# MainBoard_new.net
KiCad netlist of a schematic drawn in EAGLE
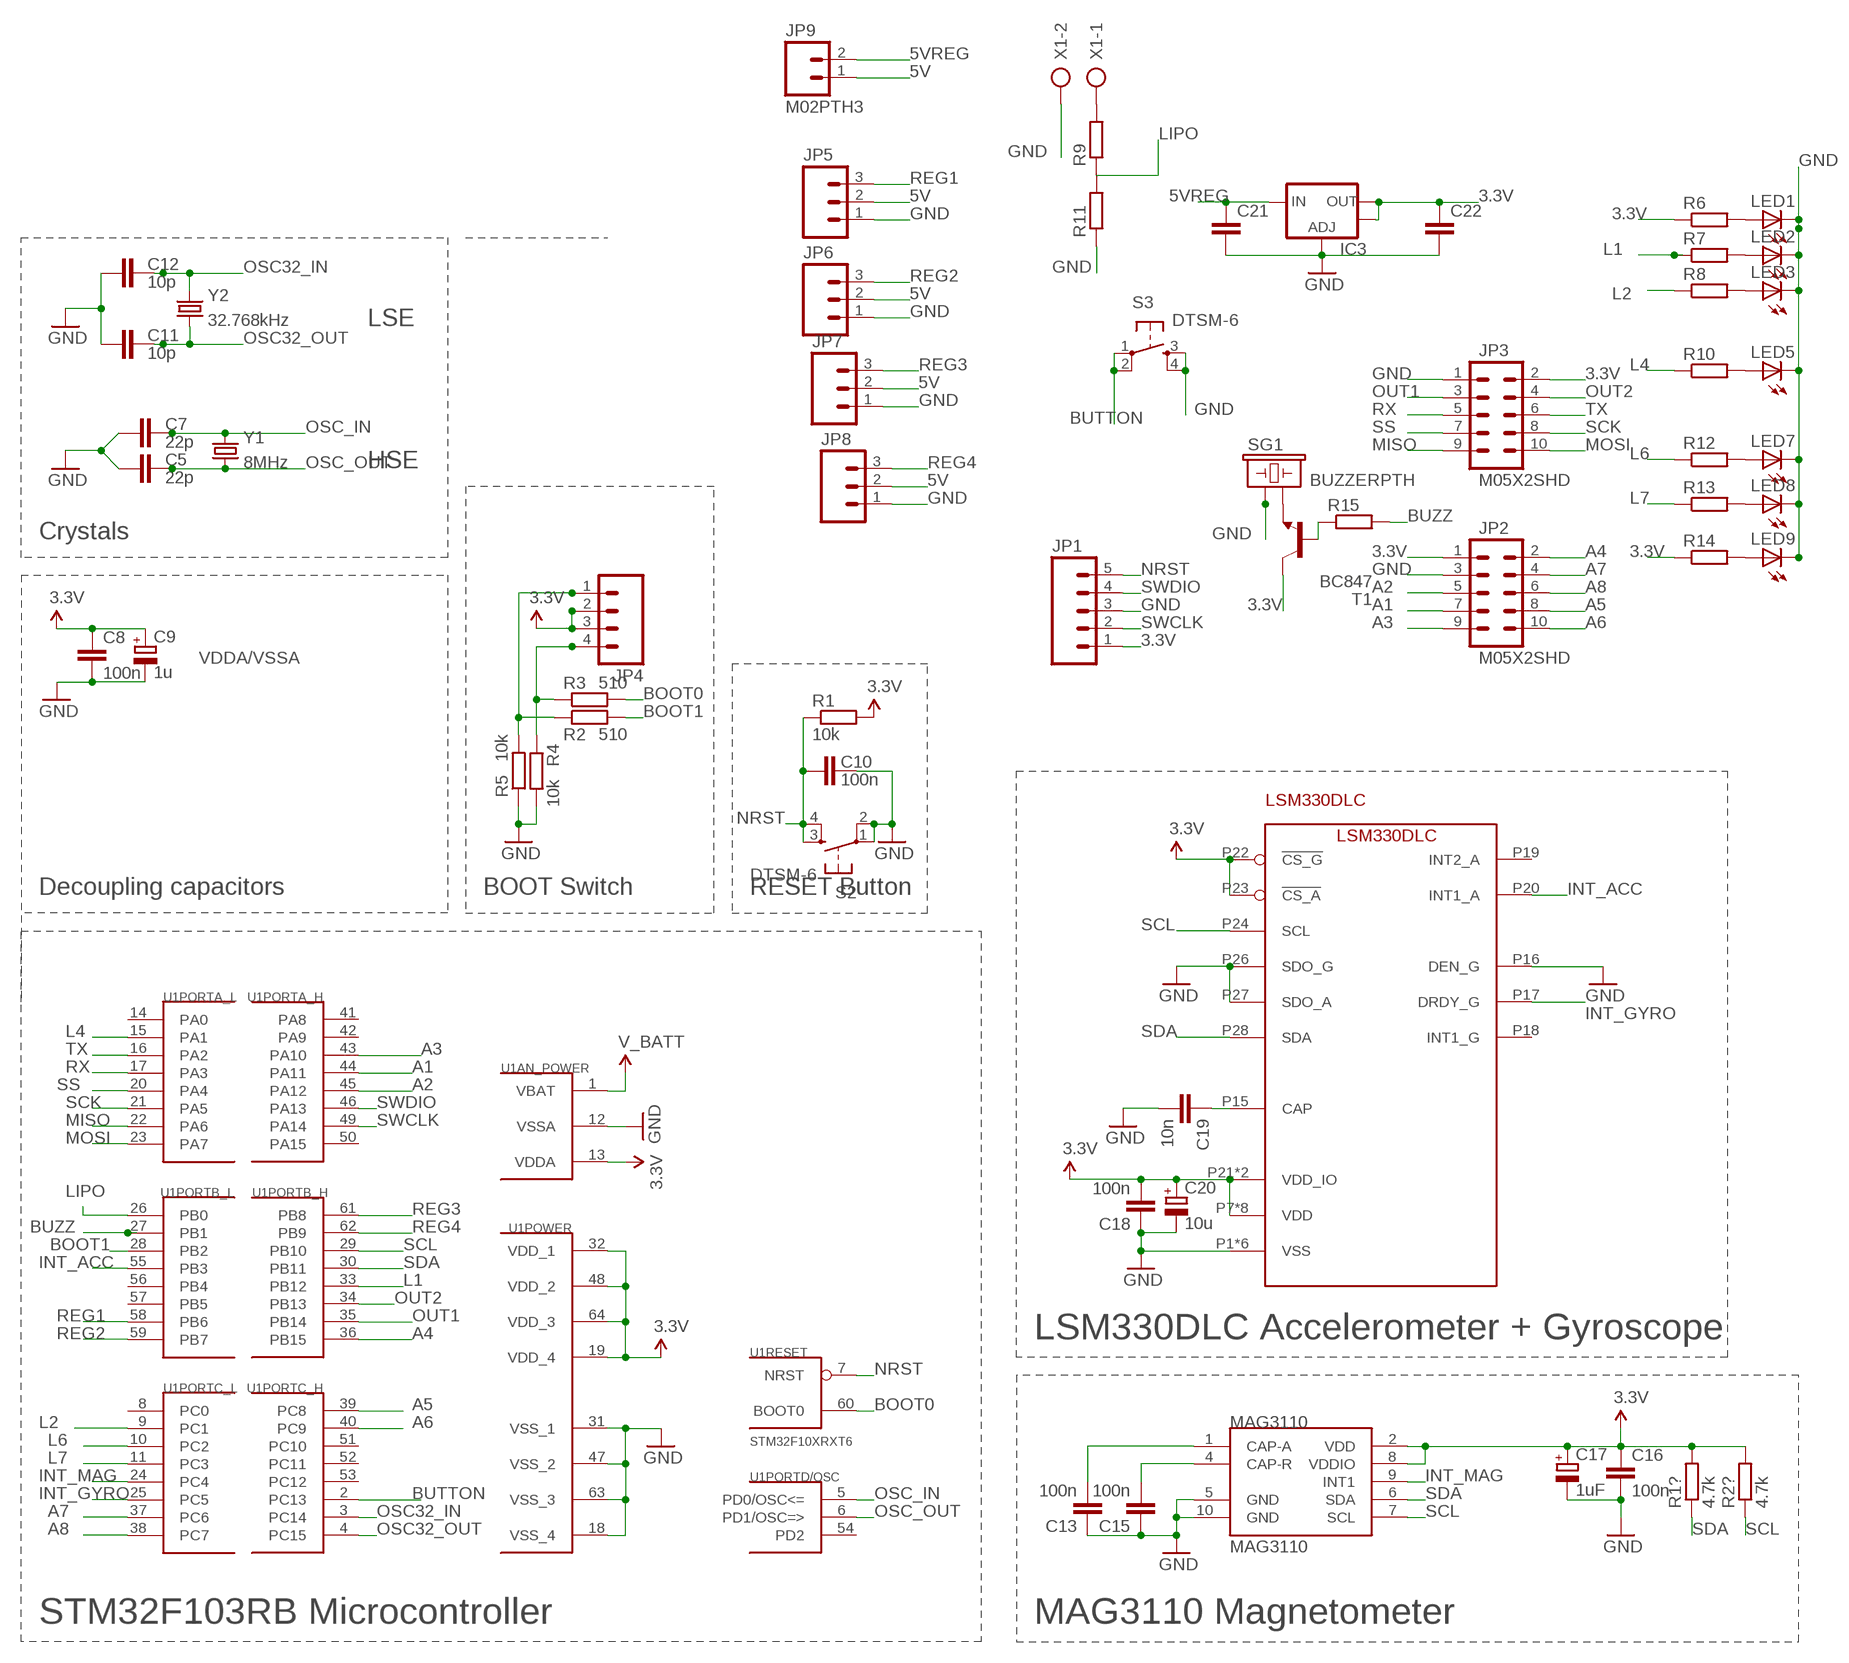
[diagram p0: schematic, sheet 1]

(export (version "E")
  (design (tool "Eeschema 10.0.6"))
  (components
    (comp (ref "C5")
      (value "22p")
      (footprint "eagle-import:C0805")
      (libsource (lib "eagle-import") (part "C-EUC0805"))
    )
    (comp (ref "C7")
      (value "22p")
      (footprint "eagle-import:C0805")
      (libsource (lib "eagle-import") (part "C-EUC0805"))
    )
    (comp (ref "C8")
      (value "100n")
      (footprint "eagle-import:C0805")
      (libsource (lib "eagle-import") (part "C-EUC0805"))
    )
    (comp (ref "C9")
      (value "1u")
      (footprint "eagle-import:SMC_A")
      (libsource (lib "eagle-import") (part "CPOL-EUSMCA"))
    )
    (comp (ref "C10")
      (value "100n")
      (footprint "eagle-import:C0805")
      (libsource (lib "eagle-import") (part "C-EUC0805"))
    )
    (comp (ref "C11")
      (value "10p")
      (footprint "eagle-import:C0805")
      (libsource (lib "eagle-import") (part "C-EUC0805"))
    )
    (comp (ref "C12")
      (value "10p")
      (footprint "eagle-import:C0805")
      (libsource (lib "eagle-import") (part "C-EUC0805"))
    )
    (comp (ref "C13")
      (value "100n")
      (footprint "eagle-import:C0805")
      (libsource (lib "eagle-import") (part "C-EUC0805"))
    )
    (comp (ref "C15")
      (value "100n")
      (footprint "eagle-import:C0805")
      (libsource (lib "eagle-import") (part "C-EUC0805"))
    )
    (comp (ref "C16")
      (value "100n")
      (footprint "eagle-import:C0805")
      (libsource (lib "eagle-import") (part "C-EUC0805"))
    )
    (comp (ref "C17")
      (value "1uF")
      (footprint "eagle-import:SMC_A")
      (libsource (lib "eagle-import") (part "CPOL-EUSMCA"))
    )
    (comp (ref "C18")
      (value "100n")
      (footprint "eagle-import:C0805")
      (libsource (lib "eagle-import") (part "resistor_C-EUC0805"))
    )
    (comp (ref "C19")
      (value "10n")
      (footprint "eagle-import:C0805")
      (libsource (lib "eagle-import") (part "resistor_C-EUC0805"))
    )
    (comp (ref "C20")
      (value "10u")
      (footprint "eagle-import:SMC_A")
      (libsource (lib "eagle-import") (part "CPOL-EUSMCA"))
    )
    (comp (ref "C21")
      (value "C-EUC0805")
      (footprint "eagle-import:C0805")
      (libsource (lib "eagle-import") (part "C-EUC0805"))
    )
    (comp (ref "C22")
      (value "C-EUC0805")
      (footprint "eagle-import:C0805")
      (libsource (lib "eagle-import") (part "C-EUC0805"))
    )
    (comp (ref "IC3")
      (value "V_REG_LM1117SOT223")
      (footprint "eagle-import:SOT223")
      (libsource (lib "eagle-import") (part "V_REG_LM1117SOT223"))
    )
    (comp (ref "JP1")
      (value "M05PTH_LONGPADS")
      (footprint "eagle-import:1X05_LONGPADS")
      (libsource (lib "eagle-import") (part "M05PTH_LONGPADS"))
    )
    (comp (ref "JP2")
      (value "M05X2SHD")
      (footprint "eagle-import:2X5-SHROUDED")
      (libsource (lib "eagle-import") (part "M05X2SHD"))
    )
    (comp (ref "JP3")
      (value "M05X2SHD")
      (footprint "eagle-import:2X5-SHROUDED")
      (libsource (lib "eagle-import") (part "M05X2SHD"))
    )
    (comp (ref "JP4")
      (value "M04LONGPADS")
      (footprint "eagle-import:1X04_LONGPADS")
      (libsource (lib "eagle-import") (part "M04LONGPADS"))
    )
    (comp (ref "JP5")
      (value "M03LONGPADS")
      (footprint "eagle-import:1X03_LONGPADS")
      (libsource (lib "eagle-import") (part "M03LONGPADS"))
    )
    (comp (ref "JP6")
      (value "M03LONGPADS")
      (footprint "eagle-import:1X03_LONGPADS")
      (libsource (lib "eagle-import") (part "M03LONGPADS"))
    )
    (comp (ref "JP7")
      (value "M03LONGPADS")
      (footprint "eagle-import:1X03_LONGPADS")
      (libsource (lib "eagle-import") (part "M03LONGPADS"))
    )
    (comp (ref "JP8")
      (value "M03LONGPADS")
      (footprint "eagle-import:1X03_LONGPADS")
      (libsource (lib "eagle-import") (part "M03LONGPADS"))
    )
    (comp (ref "JP9")
      (value "M02PTH3")
      (footprint "eagle-import:1X02_LONGPADS")
      (libsource (lib "eagle-import") (part "M02PTH3"))
    )
    (comp (ref "LED1")
      (value "LEDCHIPLED_0805")
      (footprint "eagle-import:CHIPLED_0805")
      (libsource (lib "eagle-import") (part "LEDCHIPLED_0805"))
    )
    (comp (ref "LED2")
      (value "LEDCHIPLED_0805")
      (footprint "eagle-import:CHIPLED_0805")
      (libsource (lib "eagle-import") (part "LEDCHIPLED_0805"))
    )
    (comp (ref "LED3")
      (value "LEDCHIPLED_0805")
      (footprint "eagle-import:CHIPLED_0805")
      (libsource (lib "eagle-import") (part "LEDCHIPLED_0805"))
    )
    (comp (ref "LED5")
      (value "LEDCHIPLED_0805")
      (footprint "eagle-import:CHIPLED_0805")
      (libsource (lib "eagle-import") (part "LEDCHIPLED_0805"))
    )
    (comp (ref "LED7")
      (value "LEDCHIPLED_0805")
      (footprint "eagle-import:CHIPLED_0805")
      (libsource (lib "eagle-import") (part "LEDCHIPLED_0805"))
    )
    (comp (ref "LED8")
      (value "LEDCHIPLED_0805")
      (footprint "eagle-import:CHIPLED_0805")
      (libsource (lib "eagle-import") (part "LEDCHIPLED_0805"))
    )
    (comp (ref "LED9")
      (value "LEDCHIPLED_0805")
      (footprint "eagle-import:CHIPLED_0805")
      (libsource (lib "eagle-import") (part "LEDCHIPLED_0805"))
    )
    (comp (ref "LSM330DLC")
      (value "LSM330DLC")
      (footprint "eagle-import:LGA_4X5X1P1_28L")
      (libsource (lib "eagle-import") (part "LSM330DLC"))
    )
    (comp (ref "MAG3110")
      (value "MAG3110")
      (footprint "eagle-import:DFN-10")
      (libsource (lib "eagle-import") (part "MAG3110"))
    )
    (comp (ref "R1")
      (value "10k")
      (footprint "eagle-import:R0805")
      (libsource (lib "eagle-import") (part "R-EU_R0805"))
    )
    (comp (ref "R1?")
      (value "4.7k")
      (footprint "eagle-import:R0805")
      (libsource (lib "eagle-import") (part "R-EU_R0805"))
    )
    (comp (ref "R2")
      (value "510")
      (footprint "eagle-import:R0805")
      (libsource (lib "eagle-import") (part "R-EU_R0805"))
    )
    (comp (ref "R2?")
      (value "4.7k")
      (footprint "eagle-import:R0805")
      (libsource (lib "eagle-import") (part "R-EU_R0805"))
    )
    (comp (ref "R3")
      (value "510")
      (footprint "eagle-import:R0805")
      (libsource (lib "eagle-import") (part "R-EU_R0805"))
    )
    (comp (ref "R4")
      (value "10k")
      (footprint "eagle-import:R0805")
      (libsource (lib "eagle-import") (part "R-EU_R0805"))
    )
    (comp (ref "R5")
      (value "10k")
      (footprint "eagle-import:R0805")
      (libsource (lib "eagle-import") (part "R-EU_R0805"))
    )
    (comp (ref "R6")
      (value "R-EU_M0805")
      (footprint "eagle-import:M0805")
      (libsource (lib "eagle-import") (part "resistor_R-EU_M0805"))
    )
    (comp (ref "R7")
      (value "R-EU_M0805")
      (footprint "eagle-import:M0805")
      (libsource (lib "eagle-import") (part "resistor_R-EU_M0805"))
    )
    (comp (ref "R8")
      (value "R-EU_M0805")
      (footprint "eagle-import:M0805")
      (libsource (lib "eagle-import") (part "resistor_R-EU_M0805"))
    )
    (comp (ref "R9")
      (value "R-EU_M0805")
      (footprint "eagle-import:M0805")
      (libsource (lib "eagle-import") (part "resistor_R-EU_M0805"))
    )
    (comp (ref "R10")
      (value "R-EU_M0805")
      (footprint "eagle-import:M0805")
      (libsource (lib "eagle-import") (part "resistor_R-EU_M0805"))
    )
    (comp (ref "R11")
      (value "R-EU_M0805")
      (footprint "eagle-import:M0805")
      (libsource (lib "eagle-import") (part "resistor_R-EU_M0805"))
    )
    (comp (ref "R12")
      (value "R-EU_M0805")
      (footprint "eagle-import:M0805")
      (libsource (lib "eagle-import") (part "resistor_R-EU_M0805"))
    )
    (comp (ref "R13")
      (value "R-EU_M0805")
      (footprint "eagle-import:M0805")
      (libsource (lib "eagle-import") (part "resistor_R-EU_M0805"))
    )
    (comp (ref "R14")
      (value "R-EU_M0805")
      (footprint "eagle-import:M0805")
      (libsource (lib "eagle-import") (part "resistor_R-EU_M0805"))
    )
    (comp (ref "R15")
      (value "R-EU_R0805")
      (footprint "eagle-import:R0805")
      (libsource (lib "eagle-import") (part "R-EU_R0805"))
    )
    (comp (ref "S2")
      (value "DTSM-6")
      (footprint "eagle-import:DTSM-6")
      (libsource (lib "eagle-import") (part "DTSM-6"))
    )
    (comp (ref "S3")
      (value "DTSM-6")
      (footprint "eagle-import:DTSM-6")
      (libsource (lib "eagle-import") (part "DTSM-6"))
    )
    (comp (ref "SG1")
      (value "BUZZERPTH")
      (footprint "eagle-import:BUZZER-12MM")
      (libsource (lib "eagle-import") (part "BUZZERPTH"))
    )
    (comp (ref "T1")
      (value "BC847")
      (footprint "eagle-import:SOT23")
      (libsource (lib "eagle-import") (part "BC847"))
    )
    (comp (ref "U1")
      (value "STM32F10XRXT6")
      (footprint "eagle-import:TQFP64")
      (libsource (lib "eagle-import") (part "STM32F10XRXT6"))
    )
    (comp (ref "X1")
      (value "AK300/2")
      (footprint "eagle-import:AK300_2")
      (libsource (lib "eagle-import") (part "AK300/2"))
    )
    (comp (ref "Y1")
      (value "8MHz")
      (footprint "eagle-import:HC49UP")
      (libsource (lib "eagle-import") (part "CRYSTALSMD"))
    )
    (comp (ref "Y2")
      (value "32.768kHz")
      (footprint "eagle-import:CRYSTAL-32KHZ-SMD_EPSON_MC146")
      (libsource (lib "eagle-import") (part "CRYSTALEPSONMC146"))
    )
  )
  (nets
    (net (code "1") (name "/5V") (class "Default")
      (node (ref "JP5") (pin "2") (pinfunction "2_2") (pintype "passive"))
      (node (ref "JP6") (pin "2") (pinfunction "2_2") (pintype "passive"))
      (node (ref "JP7") (pin "2") (pinfunction "2_2") (pintype "passive"))
      (node (ref "JP8") (pin "2") (pinfunction "2_2") (pintype "passive"))
      (node (ref "JP9") (pin "1") (pinfunction "1_1") (pintype "passive"))
    )
    (net (code "2") (name "/5VREG") (class "Default")
      (node (ref "C21") (pin "1") (pinfunction "1_1") (pintype "passive"))
      (node (ref "IC3") (pin "3") (pinfunction "IN_3") (pintype "input"))
      (node (ref "JP9") (pin "2") (pinfunction "2_2") (pintype "passive"))
    )
    (net (code "3") (name "/A1") (class "Default")
      (node (ref "JP2") (pin "7") (pinfunction "7_7") (pintype "passive"))
      (node (ref "U1") (pin "44") (pinfunction "PA11_44") (pintype "bidirectional"))
    )
    (net (code "4") (name "/A2") (class "Default")
      (node (ref "JP2") (pin "5") (pinfunction "5_5") (pintype "passive"))
      (node (ref "U1") (pin "45") (pinfunction "PA12_45") (pintype "bidirectional"))
    )
    (net (code "5") (name "/A3") (class "Default")
      (node (ref "JP2") (pin "9") (pinfunction "9_9") (pintype "passive"))
      (node (ref "U1") (pin "43") (pinfunction "PA10_43") (pintype "bidirectional"))
    )
    (net (code "6") (name "/A4") (class "Default")
      (node (ref "JP2") (pin "2") (pinfunction "2_2") (pintype "passive"))
      (node (ref "U1") (pin "36") (pinfunction "PB15_36") (pintype "bidirectional"))
    )
    (net (code "7") (name "/A5") (class "Default")
      (node (ref "JP2") (pin "8") (pinfunction "8_8") (pintype "passive"))
      (node (ref "U1") (pin "39") (pinfunction "PC8_39") (pintype "bidirectional"))
    )
    (net (code "8") (name "/A6") (class "Default")
      (node (ref "JP2") (pin "10") (pinfunction "10_10") (pintype "passive"))
      (node (ref "U1") (pin "40") (pinfunction "PC9_40") (pintype "bidirectional"))
    )
    (net (code "9") (name "/A7") (class "Default")
      (node (ref "JP2") (pin "4") (pinfunction "4_4") (pintype "passive"))
      (node (ref "U1") (pin "37") (pinfunction "PC6_37") (pintype "bidirectional"))
    )
    (net (code "10") (name "/A8") (class "Default")
      (node (ref "JP2") (pin "6") (pinfunction "6_6") (pintype "passive"))
      (node (ref "U1") (pin "38") (pinfunction "PC7_38") (pintype "bidirectional"))
    )
    (net (code "11") (name "/BOOT0") (class "Default")
      (node (ref "R3") (pin "2") (pinfunction "2_2") (pintype "passive"))
      (node (ref "U1") (pin "60") (pinfunction "BOOT0_60") (pintype "input"))
    )
    (net (code "12") (name "/BOOT1") (class "Default")
      (node (ref "R2") (pin "2") (pinfunction "2_2") (pintype "passive"))
      (node (ref "U1") (pin "28") (pinfunction "PB2_28") (pintype "bidirectional"))
    )
    (net (code "13") (name "/BUTTON") (class "Default")
      (node (ref "S3") (pin "1") (pinfunction "1_1") (pintype "passive"))
      (node (ref "S3") (pin "2") (pinfunction "2_2") (pintype "passive"))
      (node (ref "U1") (pin "2") (pinfunction "PC13_2") (pintype "bidirectional"))
    )
    (net (code "14") (name "/BUZZ") (class "Default")
      (node (ref "R15") (pin "2") (pinfunction "2_2") (pintype "passive"))
      (node (ref "U1") (pin "27") (pinfunction "PB1_27") (pintype "bidirectional"))
    )
    (net (code "15") (name "/INT_ACC") (class "Default")
      (node (ref "LSM330DLC") (pin "P20") (pinfunction "INT1_A_P20") (pintype "output"))
      (node (ref "U1") (pin "55") (pinfunction "PB3_55") (pintype "bidirectional"))
    )
    (net (code "16") (name "/INT_GYRO") (class "Default")
      (node (ref "LSM330DLC") (pin "P17") (pinfunction "DRDY_G_P17") (pintype "output"))
      (node (ref "U1") (pin "25") (pinfunction "PC5_25") (pintype "bidirectional"))
    )
    (net (code "17") (name "/INT_MAG") (class "Default")
      (node (ref "MAG3110") (pin "9") (pinfunction "INT1_9") (pintype "bidirectional"))
      (node (ref "U1") (pin "24") (pinfunction "PC4_24") (pintype "bidirectional"))
    )
    (net (code "18") (name "/L1") (class "Default")
      (node (ref "R7") (pin "1") (pinfunction "1_1") (pintype "passive"))
      (node (ref "U1") (pin "33") (pinfunction "PB12_33") (pintype "bidirectional"))
    )
    (net (code "19") (name "/L2") (class "Default")
      (node (ref "R8") (pin "1") (pinfunction "1_1") (pintype "passive"))
      (node (ref "U1") (pin "9") (pinfunction "PC1_9") (pintype "bidirectional"))
    )
    (net (code "20") (name "/L4") (class "Default")
      (node (ref "R10") (pin "1") (pinfunction "1_1") (pintype "passive"))
      (node (ref "U1") (pin "15") (pinfunction "PA1_15") (pintype "bidirectional"))
    )
    (net (code "21") (name "/L6") (class "Default")
      (node (ref "R12") (pin "1") (pinfunction "1_1") (pintype "passive"))
      (node (ref "U1") (pin "10") (pinfunction "PC2_10") (pintype "bidirectional"))
    )
    (net (code "22") (name "/L7") (class "Default")
      (node (ref "R13") (pin "1") (pinfunction "1_1") (pintype "passive"))
      (node (ref "U1") (pin "11") (pinfunction "PC3_11") (pintype "bidirectional"))
    )
    (net (code "23") (name "/LIPO") (class "Default")
      (node (ref "R11") (pin "2") (pinfunction "2_2") (pintype "passive"))
      (node (ref "R9") (pin "1") (pinfunction "1_1") (pintype "passive"))
      (node (ref "U1") (pin "26") (pinfunction "PB0_26") (pintype "bidirectional"))
    )
    (net (code "24") (name "/MISO") (class "Default")
      (node (ref "JP3") (pin "9") (pinfunction "9_9") (pintype "passive"))
      (node (ref "U1") (pin "22") (pinfunction "PA6_22") (pintype "bidirectional"))
    )
    (net (code "25") (name "/MOSI") (class "Default")
      (node (ref "JP3") (pin "10") (pinfunction "10_10") (pintype "passive"))
      (node (ref "U1") (pin "23") (pinfunction "PA7_23") (pintype "bidirectional"))
    )
    (net (code "26") (name "/NRST") (class "Default")
      (node (ref "C10") (pin "1") (pinfunction "1_1") (pintype "passive"))
      (node (ref "JP1") (pin "5") (pinfunction "5_5") (pintype "passive"))
      (node (ref "R1") (pin "1") (pinfunction "1_1") (pintype "passive"))
      (node (ref "S2") (pin "3") (pinfunction "3_3") (pintype "passive"))
      (node (ref "S2") (pin "4") (pinfunction "4_4") (pintype "passive"))
      (node (ref "U1") (pin "7") (pinfunction "NRST_7") (pintype "input"))
    )
    (net (code "27") (name "/OSC32_IN") (class "Default")
      (node (ref "C12") (pin "2") (pinfunction "2_2") (pintype "passive"))
      (node (ref "U1") (pin "3") (pinfunction "PC14_3") (pintype "bidirectional"))
      (node (ref "Y2") (pin "P$1") (pinfunction "2_P$1") (pintype "passive"))
    )
    (net (code "28") (name "/OSC32_OUT") (class "Default")
      (node (ref "C11") (pin "2") (pinfunction "2_2") (pintype "passive"))
      (node (ref "U1") (pin "4") (pinfunction "PC15_4") (pintype "bidirectional"))
      (node (ref "Y2") (pin "P$2") (pinfunction "1_P$2") (pintype "passive"))
    )
    (net (code "29") (name "/OSC_IN") (class "Default")
      (node (ref "C7") (pin "2") (pinfunction "2_2") (pintype "passive"))
      (node (ref "U1") (pin "5") (pinfunction "PD0/OSC<=_5") (pintype "bidirectional"))
      (node (ref "Y1") (pin "2") (pinfunction "2_2") (pintype "passive"))
    )
    (net (code "30") (name "/OSC_OUT") (class "Default")
      (node (ref "C5") (pin "2") (pinfunction "2_2") (pintype "passive"))
      (node (ref "U1") (pin "6") (pinfunction "PD1/OSC=>_6") (pintype "bidirectional"))
      (node (ref "Y1") (pin "1") (pinfunction "1_1") (pintype "passive"))
    )
    (net (code "31") (name "/OUT1") (class "Default")
      (node (ref "JP3") (pin "3") (pinfunction "3_3") (pintype "passive"))
      (node (ref "U1") (pin "35") (pinfunction "PB14_35") (pintype "bidirectional"))
    )
    (net (code "32") (name "/OUT2") (class "Default")
      (node (ref "JP3") (pin "4") (pinfunction "4_4") (pintype "passive"))
      (node (ref "U1") (pin "34") (pinfunction "PB13_34") (pintype "bidirectional"))
    )
    (net (code "33") (name "/REG1") (class "Default")
      (node (ref "JP5") (pin "3") (pinfunction "3_3") (pintype "passive"))
      (node (ref "U1") (pin "58") (pinfunction "PB6_58") (pintype "bidirectional"))
    )
    (net (code "34") (name "/REG2") (class "Default")
      (node (ref "JP6") (pin "3") (pinfunction "3_3") (pintype "passive"))
      (node (ref "U1") (pin "59") (pinfunction "PB7_59") (pintype "bidirectional"))
    )
    (net (code "35") (name "/REG3") (class "Default")
      (node (ref "JP7") (pin "3") (pinfunction "3_3") (pintype "passive"))
      (node (ref "U1") (pin "61") (pinfunction "PB8_61") (pintype "bidirectional"))
    )
    (net (code "36") (name "/REG4") (class "Default")
      (node (ref "JP8") (pin "3") (pinfunction "3_3") (pintype "passive"))
      (node (ref "U1") (pin "62") (pinfunction "PB9_62") (pintype "bidirectional"))
    )
    (net (code "37") (name "/RX") (class "Default")
      (node (ref "JP3") (pin "5") (pinfunction "5_5") (pintype "passive"))
      (node (ref "U1") (pin "17") (pinfunction "PA3_17") (pintype "bidirectional"))
    )
    (net (code "38") (name "/SCK") (class "Default")
      (node (ref "JP3") (pin "8") (pinfunction "8_8") (pintype "passive"))
      (node (ref "U1") (pin "21") (pinfunction "PA5_21") (pintype "bidirectional"))
    )
    (net (code "39") (name "/SCL") (class "Default")
      (node (ref "LSM330DLC") (pin "P24") (pinfunction "SCL_P24") (pintype "input"))
      (node (ref "MAG3110") (pin "7") (pinfunction "SCL_7") (pintype "bidirectional"))
      (node (ref "R2?") (pin "1") (pinfunction "1_1") (pintype "passive"))
      (node (ref "U1") (pin "29") (pinfunction "PB10_29") (pintype "bidirectional"))
    )
    (net (code "40") (name "/SDA") (class "Default")
      (node (ref "LSM330DLC") (pin "P28") (pinfunction "SDA_P28") (pintype "input"))
      (node (ref "MAG3110") (pin "6") (pinfunction "SDA_6") (pintype "bidirectional"))
      (node (ref "R1?") (pin "1") (pinfunction "1_1") (pintype "passive"))
      (node (ref "U1") (pin "30") (pinfunction "PB11_30") (pintype "bidirectional"))
    )
    (net (code "41") (name "/SS") (class "Default")
      (node (ref "JP3") (pin "7") (pinfunction "7_7") (pintype "passive"))
      (node (ref "U1") (pin "20") (pinfunction "PA4_20") (pintype "bidirectional"))
    )
    (net (code "42") (name "/SWCLK") (class "Default")
      (node (ref "JP1") (pin "2") (pinfunction "2_2") (pintype "passive"))
      (node (ref "U1") (pin "49") (pinfunction "PA14_49") (pintype "bidirectional"))
    )
    (net (code "43") (name "/SWDIO") (class "Default")
      (node (ref "JP1") (pin "4") (pinfunction "4_4") (pintype "passive"))
      (node (ref "U1") (pin "46") (pinfunction "PA13_46") (pintype "bidirectional"))
    )
    (net (code "44") (name "/TX") (class "Default")
      (node (ref "JP3") (pin "6") (pinfunction "6_6") (pintype "passive"))
      (node (ref "U1") (pin "16") (pinfunction "PA2_16") (pintype "bidirectional"))
    )
    (net (code "45") (name "3.3V") (class "Default")
      (node (ref "C16") (pin "1") (pinfunction "1_1") (pintype "passive"))
      (node (ref "C17") (pin "+") (pinfunction "+_+") (pintype "passive"))
      (node (ref "C18") (pin "2") (pinfunction "2_2") (pintype "passive"))
      (node (ref "C20") (pin "+") (pinfunction "+_+") (pintype "passive"))
      (node (ref "C22") (pin "1") (pinfunction "1_1") (pintype "passive"))
      (node (ref "C8") (pin "1") (pinfunction "1_1") (pintype "passive"))
      (node (ref "C9") (pin "+") (pinfunction "+_+") (pintype "passive"))
      (node (ref "IC3") (pin "2") (pinfunction "OUT_2") (pintype "output"))
      (node (ref "IC3") (pin "4") (pinfunction "OUT_4") (pintype "output"))
      (node (ref "JP1") (pin "1") (pinfunction "1_1") (pintype "passive"))
      (node (ref "JP2") (pin "1") (pinfunction "1_1") (pintype "passive"))
      (node (ref "JP3") (pin "2") (pinfunction "2_2") (pintype "passive"))
      (node (ref "JP4") (pin "2") (pinfunction "2_2") (pintype "passive"))
      (node (ref "JP4") (pin "3") (pinfunction "3_3") (pintype "passive"))
      (node (ref "LSM330DLC") (pin "P10") (pinfunction "VDD_P10") (pintype "power_in"))
      (node (ref "LSM330DLC") (pin "P11") (pinfunction "VDD_P11") (pintype "power_in"))
      (node (ref "LSM330DLC") (pin "P12") (pinfunction "VDD_P12") (pintype "power_in"))
      (node (ref "LSM330DLC") (pin "P13") (pinfunction "VDD_P13") (pintype "power_in"))
      (node (ref "LSM330DLC") (pin "P14") (pinfunction "VDD_P14") (pintype "power_in"))
      (node (ref "LSM330DLC") (pin "P21") (pinfunction "VDD_IO_P21") (pintype "power_in"))
      (node (ref "LSM330DLC") (pin "P22") (pinfunction "~{CS_G}_P22") (pintype "input"))
      (node (ref "LSM330DLC") (pin "P23") (pinfunction "~{CS_A}_P23") (pintype "input"))
      (node (ref "LSM330DLC") (pin "P25") (pinfunction "VDD_IO_P25") (pintype "power_in"))
      (node (ref "LSM330DLC") (pin "P7") (pinfunction "VDD_P7") (pintype "power_in"))
      (node (ref "LSM330DLC") (pin "P8") (pinfunction "VDD_P8") (pintype "power_in"))
      (node (ref "LSM330DLC") (pin "P9") (pinfunction "VDD_P9") (pintype "power_in"))
      (node (ref "MAG3110") (pin "2") (pinfunction "VDD_2") (pintype "bidirectional"))
      (node (ref "MAG3110") (pin "8") (pinfunction "VDDIO_8") (pintype "bidirectional"))
      (node (ref "R1") (pin "2") (pinfunction "2_2") (pintype "passive"))
      (node (ref "R14") (pin "1") (pinfunction "1_1") (pintype "passive"))
      (node (ref "R1?") (pin "2") (pinfunction "2_2") (pintype "passive"))
      (node (ref "R2?") (pin "2") (pinfunction "2_2") (pintype "passive"))
      (node (ref "R6") (pin "1") (pinfunction "1_1") (pintype "passive"))
      (node (ref "T1") (pin "3") (pinfunction "C_3") (pintype "passive"))
      (node (ref "U1") (pin "13") (pinfunction "VDDA_13") (pintype "power_in"))
      (node (ref "U1") (pin "19") (pinfunction "VDD_4_19") (pintype "power_in"))
      (node (ref "U1") (pin "32") (pinfunction "VDD_1_32") (pintype "power_in"))
      (node (ref "U1") (pin "48") (pinfunction "VDD_2_48") (pintype "power_in"))
      (node (ref "U1") (pin "64") (pinfunction "VDD_3_64") (pintype "power_in"))
    )
    (net (code "46") (name "GND") (class "Default")
      (node (ref "C10") (pin "2") (pinfunction "2_2") (pintype "passive"))
      (node (ref "C11") (pin "1") (pinfunction "1_1") (pintype "passive"))
      (node (ref "C12") (pin "1") (pinfunction "1_1") (pintype "passive"))
      (node (ref "C13") (pin "1") (pinfunction "1_1") (pintype "passive"))
      (node (ref "C15") (pin "1") (pinfunction "1_1") (pintype "passive"))
      (node (ref "C16") (pin "2") (pinfunction "2_2") (pintype "passive"))
      (node (ref "C17") (pin "-") (pinfunction "-_-") (pintype "passive"))
      (node (ref "C18") (pin "1") (pinfunction "1_1") (pintype "passive"))
      (node (ref "C19") (pin "2") (pinfunction "2_2") (pintype "passive"))
      (node (ref "C20") (pin "-") (pinfunction "-_-") (pintype "passive"))
      (node (ref "C21") (pin "2") (pinfunction "2_2") (pintype "passive"))
      (node (ref "C22") (pin "2") (pinfunction "2_2") (pintype "passive"))
      (node (ref "C5") (pin "1") (pinfunction "1_1") (pintype "passive"))
      (node (ref "C7") (pin "1") (pinfunction "1_1") (pintype "passive"))
      (node (ref "C8") (pin "2") (pinfunction "2_2") (pintype "passive"))
      (node (ref "C9") (pin "-") (pinfunction "-_-") (pintype "passive"))
      (node (ref "IC3") (pin "1") (pinfunction "ADJ_1") (pintype "input"))
      (node (ref "JP1") (pin "3") (pinfunction "3_3") (pintype "passive"))
      (node (ref "JP2") (pin "3") (pinfunction "3_3") (pintype "passive"))
      (node (ref "JP3") (pin "1") (pinfunction "1_1") (pintype "passive"))
      (node (ref "JP5") (pin "1") (pinfunction "1_1") (pintype "passive"))
      (node (ref "JP6") (pin "1") (pinfunction "1_1") (pintype "passive"))
      (node (ref "JP7") (pin "1") (pinfunction "1_1") (pintype "passive"))
      (node (ref "JP8") (pin "1") (pinfunction "1_1") (pintype "passive"))
      (node (ref "LED1") (pin "C") (pinfunction "C_C") (pintype "passive"))
      (node (ref "LED2") (pin "C") (pinfunction "C_C") (pintype "passive"))
      (node (ref "LED3") (pin "C") (pinfunction "C_C") (pintype "passive"))
      (node (ref "LED5") (pin "C") (pinfunction "C_C") (pintype "passive"))
      (node (ref "LED7") (pin "C") (pinfunction "C_C") (pintype "passive"))
      (node (ref "LED8") (pin "C") (pinfunction "C_C") (pintype "passive"))
      (node (ref "LED9") (pin "C") (pinfunction "C_C") (pintype "passive"))
      (node (ref "LSM330DLC") (pin "P1") (pinfunction "VSS_P1") (pintype "power_in"))
      (node (ref "LSM330DLC") (pin "P16") (pinfunction "DEN_G_P16") (pintype "input"))
      (node (ref "LSM330DLC") (pin "P2") (pinfunction "VSS_P2") (pintype "power_in"))
      (node (ref "LSM330DLC") (pin "P26") (pinfunction "SDO_G_P26") (pintype "output"))
      (node (ref "LSM330DLC") (pin "P27") (pinfunction "SDO_A_P27") (pintype "output"))
      (node (ref "LSM330DLC") (pin "P3") (pinfunction "VSS_P3") (pintype "power_in"))
      (node (ref "LSM330DLC") (pin "P4") (pinfunction "VSS_P4") (pintype "power_in"))
      (node (ref "LSM330DLC") (pin "P5") (pinfunction "VSS_P5") (pintype "power_in"))
      (node (ref "LSM330DLC") (pin "P6") (pinfunction "VSS_P6") (pintype "power_in"))
      (node (ref "MAG3110") (pin "10") (pinfunction "GND_10") (pintype "bidirectional"))
      (node (ref "MAG3110") (pin "5") (pinfunction "GND_5") (pintype "bidirectional"))
      (node (ref "R11") (pin "1") (pinfunction "1_1") (pintype "passive"))
      (node (ref "R4") (pin "2") (pinfunction "2_2") (pintype "passive"))
      (node (ref "R5") (pin "1") (pinfunction "1_1") (pintype "passive"))
      (node (ref "S2") (pin "1") (pinfunction "1_1") (pintype "passive"))
      (node (ref "S2") (pin "2") (pinfunction "2_2") (pintype "passive"))
      (node (ref "S3") (pin "3") (pinfunction "3_3") (pintype "passive"))
      (node (ref "S3") (pin "4") (pinfunction "4_4") (pintype "passive"))
      (node (ref "SG1") (pin "+") (pinfunction "1_+") (pintype "passive"))
      (node (ref "U1") (pin "12") (pinfunction "VSSA_12") (pintype "power_in"))
      (node (ref "U1") (pin "18") (pinfunction "VSS_4_18") (pintype "power_in"))
      (node (ref "U1") (pin "31") (pinfunction "VSS_1_31") (pintype "power_in"))
      (node (ref "U1") (pin "47") (pinfunction "VSS_2_47") (pintype "power_in"))
      (node (ref "U1") (pin "63") (pinfunction "VSS_3_63") (pintype "power_in"))
      (node (ref "X1") (pin "2") (pinfunction "KL_2") (pintype "passive"))
    )
    (net (code "47") (name "Net-(JP4-Pad1)") (class "Default")
      (node (ref "JP4") (pin "1") (pinfunction "1_1") (pintype "passive"))
      (node (ref "R2") (pin "1") (pinfunction "1_1") (pintype "passive"))
      (node (ref "R5") (pin "2") (pinfunction "2_2") (pintype "passive"))
    )
    (net (code "48") (name "Net-(JP4-Pad4)") (class "Default")
      (node (ref "JP4") (pin "4") (pinfunction "4_4") (pintype "passive"))
      (node (ref "R3") (pin "1") (pinfunction "1_1") (pintype "passive"))
      (node (ref "R4") (pin "1") (pinfunction "1_1") (pintype "passive"))
    )
    (net (code "49") (name "Net-(LED1-PadA)") (class "Default")
      (node (ref "LED1") (pin "A") (pinfunction "A_A") (pintype "passive"))
      (node (ref "R6") (pin "2") (pinfunction "2_2") (pintype "passive"))
    )
    (net (code "50") (name "Net-(LED2-PadA)") (class "Default")
      (node (ref "LED2") (pin "A") (pinfunction "A_A") (pintype "passive"))
      (node (ref "R7") (pin "2") (pinfunction "2_2") (pintype "passive"))
    )
    (net (code "51") (name "Net-(LED3-PadA)") (class "Default")
      (node (ref "LED3") (pin "A") (pinfunction "A_A") (pintype "passive"))
      (node (ref "R8") (pin "2") (pinfunction "2_2") (pintype "passive"))
    )
    (net (code "52") (name "Net-(LED5-PadA)") (class "Default")
      (node (ref "LED5") (pin "A") (pinfunction "A_A") (pintype "passive"))
      (node (ref "R10") (pin "2") (pinfunction "2_2") (pintype "passive"))
    )
    (net (code "53") (name "Net-(LED7-PadA)") (class "Default")
      (node (ref "LED7") (pin "A") (pinfunction "A_A") (pintype "passive"))
      (node (ref "R12") (pin "2") (pinfunction "2_2") (pintype "passive"))
    )
    (net (code "54") (name "Net-(LED8-PadA)") (class "Default")
      (node (ref "LED8") (pin "A") (pinfunction "A_A") (pintype "passive"))
      (node (ref "R13") (pin "2") (pinfunction "2_2") (pintype "passive"))
    )
    (net (code "55") (name "Net-(LED9-PadA)") (class "Default")
      (node (ref "LED9") (pin "A") (pinfunction "A_A") (pintype "passive"))
      (node (ref "R14") (pin "2") (pinfunction "2_2") (pintype "passive"))
    )
    (net (code "56") (name "Net-(LSM330DLC-CAP)") (class "Default")
      (node (ref "C19") (pin "1") (pinfunction "1_1") (pintype "passive"))
      (node (ref "LSM330DLC") (pin "P15") (pinfunction "CAP_P15") (pintype "power_in"))
    )
    (net (code "57") (name "Net-(MAG3110-CAP-A)") (class "Default")
      (node (ref "C13") (pin "2") (pinfunction "2_2") (pintype "passive"))
      (node (ref "MAG3110") (pin "1") (pinfunction "CAP-A_1") (pintype "bidirectional"))
    )
    (net (code "58") (name "Net-(MAG3110-CAP-R)") (class "Default")
      (node (ref "C15") (pin "2") (pinfunction "2_2") (pintype "passive"))
      (node (ref "MAG3110") (pin "4") (pinfunction "CAP-R_4") (pintype "bidirectional"))
    )
    (net (code "59") (name "Net-(SG1-2)") (class "Default")
      (node (ref "SG1") (pin "-") (pinfunction "2_-") (pintype "passive"))
      (node (ref "T1") (pin "2") (pinfunction "E_2") (pintype "passive"))
    )
    (net (code "60") (name "Net-(T1-B)") (class "Default")
      (node (ref "R15") (pin "1") (pinfunction "1_1") (pintype "passive"))
      (node (ref "T1") (pin "1") (pinfunction "B_1") (pintype "passive"))
    )
    (net (code "61") (name "Net-(X1A-KL)") (class "Default")
      (node (ref "R9") (pin "2") (pinfunction "2_2") (pintype "passive"))
      (node (ref "X1") (pin "1") (pinfunction "KL_1") (pintype "passive"))
    )
    (net (code "62") (name "V_BATT") (class "Default")
      (node (ref "U1") (pin "1") (pinfunction "VBAT_1") (pintype "power_in"))
    )
    (net (code "63") (name "unconnected-(LSM330DLC-INT1_G-PadP18)") (class "Default")
      (node (ref "LSM330DLC") (pin "P18") (pinfunction "INT1_G_P18") (pintype "output"))
    )
    (net (code "64") (name "unconnected-(LSM330DLC-INT2_A-PadP19)") (class "Default")
      (node (ref "LSM330DLC") (pin "P19") (pinfunction "INT2_A_P19") (pintype "output"))
    )
    (net (code "65") (name "unconnected-(U1B-PA8-Pad41)") (class "Default")
      (node (ref "U1") (pin "41") (pinfunction "PA8_41") (pintype "bidirectional"))
    )
    (net (code "66") (name "unconnected-(U1B-PA9-Pad42)") (class "Default")
      (node (ref "U1") (pin "42") (pinfunction "PA9_42") (pintype "bidirectional"))
    )
    (net (code "67") (name "unconnected-(U1B-PA15-Pad50)") (class "Default")
      (node (ref "U1") (pin "50") (pinfunction "PA15_50") (pintype "bidirectional"))
    )
    (net (code "68") (name "unconnected-(U1C-PA0-Pad14)") (class "Default")
      (node (ref "U1") (pin "14") (pinfunction "PA0_14") (pintype "bidirectional"))
    )
    (net (code "69") (name "unconnected-(U1E-PB4-Pad56)") (class "Default")
      (node (ref "U1") (pin "56") (pinfunction "PB4_56") (pintype "bidirectional"))
    )
    (net (code "70") (name "unconnected-(U1E-PB5-Pad57)") (class "Default")
      (node (ref "U1") (pin "57") (pinfunction "PB5_57") (pintype "bidirectional"))
    )
    (net (code "71") (name "unconnected-(U1F-PC10-Pad51)") (class "Default")
      (node (ref "U1") (pin "51") (pinfunction "PC10_51") (pintype "bidirectional"))
    )
    (net (code "72") (name "unconnected-(U1F-PC11-Pad52)") (class "Default")
      (node (ref "U1") (pin "52") (pinfunction "PC11_52") (pintype "bidirectional"))
    )
    (net (code "73") (name "unconnected-(U1F-PC12-Pad53)") (class "Default")
      (node (ref "U1") (pin "53") (pinfunction "PC12_53") (pintype "bidirectional"))
    )
    (net (code "74") (name "unconnected-(U1G-PC0-Pad8)") (class "Default")
      (node (ref "U1") (pin "8") (pinfunction "PC0_8") (pintype "bidirectional"))
    )
    (net (code "75") (name "unconnected-(U1H-PD2-Pad54)") (class "Default")
      (node (ref "U1") (pin "54") (pinfunction "PD2_54") (pintype "bidirectional"))
    )
  )
)
